# IO_and_Connectors.net
KiCad netlist of a schematic drawn in Altium Designer
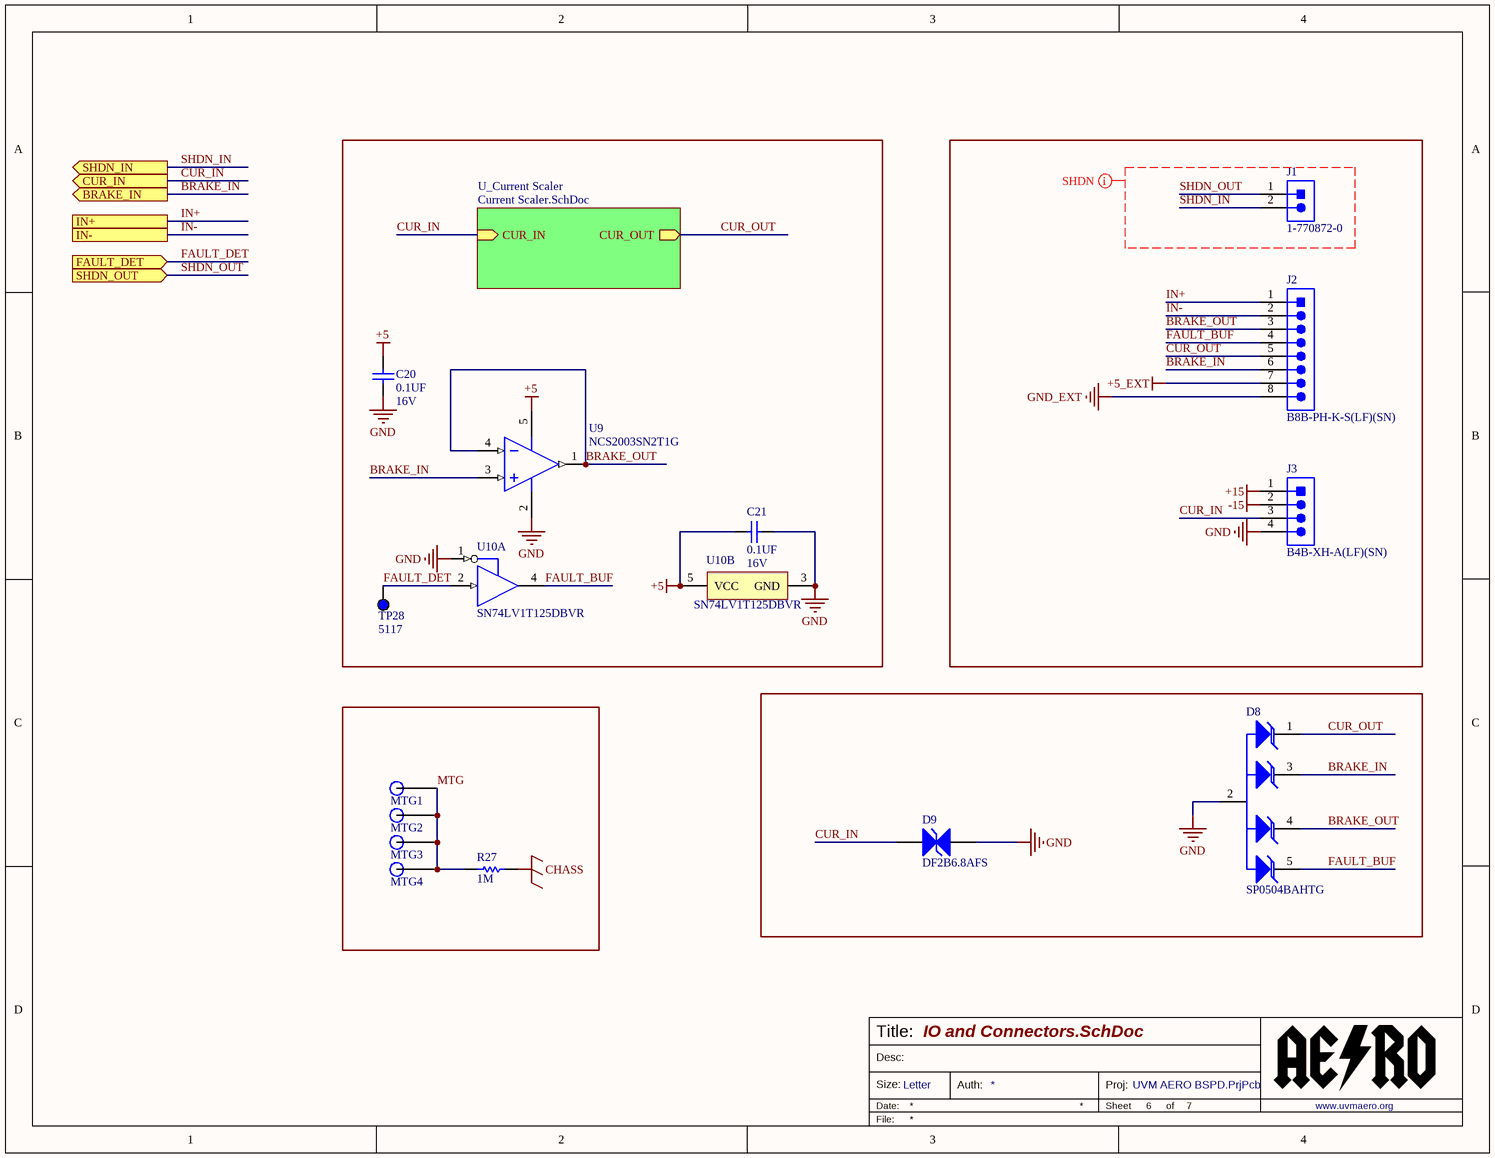
[diagram p0: IO and Connectors.SchDoc]

(export (version "E")
  (design (tool "Eeschema 10.0.6"))
  (components
    (comp (ref "C20")
      (value "CAP 0603 0.1UF 16V 10% X7R")
      (footprint "0603_CAP")
      (description "Capacitor Surface Mount 0603 Footprint 0.1UF 16V 10% Tolerance Ceramic X7R")
      (fields
        (field (name "VAL") "0.1UF")
        (field (name "VOL") "16V")
        (field (name "MANUFACTURER") "Various")
        (field (name "VOLTAGE") "16V")
      )
      (libsource (lib "Passive Components") (part "cap"))
    )
    (comp (ref "C21")
      (value "CAP 0603 0.1UF 16V 10% X7R")
      (footprint "0603_CAP")
      (description "Capacitor Surface Mount 0603 Footprint 0.1UF 16V 10% Tolerance Ceramic X7R")
      (fields
        (field (name "VAL") "0.1UF")
        (field (name "VOL") "16V")
        (field (name "MANUFACTURER") "Various")
        (field (name "VOLTAGE") "16V")
      )
      (libsource (lib "Passive Components") (part "cap"))
    )
    (comp (ref "D8")
      (value "SP0504BAHTG")
      (footprint "SOT23127P600-8N")
      (description "8.5V Clamp  Ipp Tvs Diode Surface Mount SOT-23-5 5.5V")
      (fields (field (name "MANUFACTURER") "Littelfuse"))
      (libsource (lib "bspd parts") (part "SP0504BAHTG"))
    )
    (comp (ref "D9")
      (value "DF2B6.8AFS")
      (footprint "SOD923")
      (description "7V (Typ) Clamp 1A (8/20µs) Ipp Tvs Diode Surface Mount fSC (SOD-923)")
      (libsource (lib "bspd parts") (part "DF2B6.8AFS"))
    )
    (comp (ref "J1")
      (value "1-770872-0")
      (footprint "CON2_1X2_P163_VM_ALT")
      (description "Connector Header Through Hole 2 position 0.163\" (4.14mm)")
      (fields (field (name "COPYRIGHT") "Copyright (C) 2018 Accelerated Designs. All rights reserved"))
      (libsource (lib "bspd parts") (part "1-770872-0"))
    )
    (comp (ref "J2")
      (value "B8B-PH-K-S(LF)(SN)")
      (footprint "B8B-PH-K")
      (description "Connector Header Through Hole 8 position 0.079\" (2.00mm)")
      (libsource (lib "bspd parts") (part "B8B-PH-K-S(LF)(SN)"))
    )
    (comp (ref "J3")
      (value "B4B-XH-A(LF)(SN)")
      (footprint "B4B-XH-A(LF)(SN)")
      (description "Connector Header Through Hole 4 position 0.098\" (2.50mm)")
      (fields (field (name "MANUFACTURER") "JST"))
      (libsource (lib "bspd parts") (part "B4B-XH-A(LF)(SN)"))
    )
    (comp (ref "MTG1")
      (value "PCB MTG M3")
      (footprint "MTG-M3")
      (description "PCB Mounting for M3 Screw")
      (libsource (lib "Hardware") (part "MTG"))
    )
    (comp (ref "MTG2")
      (value "PCB MTG M3")
      (footprint "MTG-M3")
      (description "PCB Mounting for M3 Screw")
      (libsource (lib "Hardware") (part "MTG"))
    )
    (comp (ref "MTG3")
      (value "PCB MTG M3")
      (footprint "MTG-M3")
      (description "PCB Mounting for M3 Screw")
      (libsource (lib "Hardware") (part "MTG"))
    )
    (comp (ref "MTG4")
      (value "PCB MTG M3")
      (footprint "MTG-M3")
      (description "PCB Mounting for M3 Screw")
      (libsource (lib "Hardware") (part "MTG"))
    )
    (comp (ref "R27")
      (value "1M")
      (footprint "RESC2013X60X35ML10T20")
      (fields (field (name "MANUFACTURER") "Yageo") (field (name "PART NUMBER") "RT0805BRE071ML"))
      (libsource (lib "Altium Content Vault") (part "RES"))
    )
    (comp (ref "TP28")
      (value "5117")
      (footprint "KSTN-5117")
      (description "Test Point, Blue, 1-Pin THD, RoHS, Bulk")
      (fields (field (name "MANUFACTURER") "KeystoneElectronics"))
      (libsource (lib "bspd parts") (part "5117"))
    )
    (comp (ref "U9")
      (value "NCS2003SN2T1G")
      (footprint "ONSC-TSOP-5-483-02_V")
      (fields (field (name "MANUFACTURER") "On Semiconductor"))
      (libsource (lib "Altium Content Vault") (part "ONSC-NCS2003-TSOP-5-483-02"))
    )
    (comp (ref "U10")
      (value "SN74LV1T125DBVR")
      (footprint "DBV0005A_M")
      (description "Single Power Supply, Single BUFFER GATE w/ 3-State Output (active low enable), DBV0005A, LARGE T&R")
      (fields
        (field (name "GENERIC PART NUMBER") "SN74LV1T125")
        (field (name "MANUFACTURER") "Texas Instruments")
      )
      (libsource (lib "Altium Content Vault") (part "TI-SN74AXXXX1X125-5"))
    )
  )
  (nets
    (net (code "1") (name "+5") (class "Default")
      (node (ref "C20") (pin "2") (pinfunction "2_2") (pintype "passive"))
      (node (ref "C21") (pin "2") (pinfunction "2_2") (pintype "passive"))
      (node (ref "U10") (pin "5") (pinfunction "VCC_5") (pintype "power_in"))
      (node (ref "U9") (pin "5") (pinfunction "VDD_5") (pintype "power_in"))
    )
    (net (code "2") (name "+5_EXT") (class "Default")
      (node (ref "J2") (pin "7") (pinfunction "7_7") (pintype "passive"))
    )
    (net (code "3") (name "+15") (class "Default")
      (node (ref "J3") (pin "1") (pinfunction "1_1") (pintype "passive"))
    )
    (net (code "4") (name "-15") (class "Default")
      (node (ref "J3") (pin "2") (pinfunction "2_2") (pintype "passive"))
    )
    (net (code "5") (name "/BRAKE_IN") (class "Default")
      (node (ref "D8") (pin "3") (pinfunction "3_3") (pintype "passive"))
      (node (ref "J2") (pin "6") (pinfunction "6_6") (pintype "passive"))
      (node (ref "U9") (pin "3") (pinfunction "IN+_3") (pintype "input"))
    )
    (net (code "6") (name "/BRAKE_OUT") (class "Default")
      (node (ref "D8") (pin "4") (pinfunction "4_4") (pintype "passive"))
      (node (ref "J2") (pin "3") (pinfunction "3_3") (pintype "passive"))
      (node (ref "U9") (pin "1") (pinfunction "VOUT_1") (pintype "output"))
      (node (ref "U9") (pin "4") (pinfunction "IN-_4") (pintype "input"))
    )
    (net (code "7") (name "/CUR_IN") (class "Default")
      (node (ref "D9") (pin "1") (pinfunction "A1_1") (pintype "passive"))
      (node (ref "J3") (pin "3") (pinfunction "3_3") (pintype "passive"))
    )
    (net (code "8") (name "/CUR_OUT") (class "Default")
      (node (ref "D8") (pin "1") (pinfunction "1_1") (pintype "passive"))
      (node (ref "J2") (pin "5") (pinfunction "5_5") (pintype "passive"))
    )
    (net (code "9") (name "/FAULT_BUF") (class "Default")
      (node (ref "D8") (pin "5") (pinfunction "5_5") (pintype "passive"))
      (node (ref "J2") (pin "4") (pinfunction "4_4") (pintype "passive"))
      (node (ref "U10") (pin "4") (pinfunction "Y_4") (pintype "tri_state"))
    )
    (net (code "10") (name "/FAULT_DET") (class "Default")
      (node (ref "TP28") (pin "1") (pintype "passive"))
      (node (ref "U10") (pin "2") (pinfunction "A_2") (pintype "input"))
    )
    (net (code "11") (name "/IN+") (class "Default")
      (node (ref "J2") (pin "1") (pinfunction "1_1") (pintype "passive"))
    )
    (net (code "12") (name "/IN-") (class "Default")
      (node (ref "J2") (pin "2") (pinfunction "2_2") (pintype "passive"))
    )
    (net (code "13") (name "/MTG") (class "Default")
      (node (ref "MTG1") (pin "1") (pinfunction "1_1") (pintype "passive"))
      (node (ref "MTG2") (pin "1") (pinfunction "1_1") (pintype "passive"))
      (node (ref "MTG3") (pin "1") (pinfunction "1_1") (pintype "passive"))
      (node (ref "MTG4") (pin "1") (pinfunction "1_1") (pintype "passive"))
      (node (ref "R27") (pin "2") (pinfunction "2_2") (pintype "passive"))
    )
    (net (code "14") (name "/SHDN_IN") (class "Default")
      (node (ref "J1") (pin "2") (pinfunction "2_2") (pintype "passive"))
    )
    (net (code "15") (name "/SHDN_OUT") (class "Default")
      (node (ref "J1") (pin "1") (pinfunction "1_1") (pintype "passive"))
    )
    (net (code "16") (name "CHASS") (class "Default")
      (node (ref "R27") (pin "1") (pinfunction "1_1") (pintype "passive"))
    )
    (net (code "17") (name "GND") (class "Default")
      (node (ref "C20") (pin "1") (pinfunction "1_1") (pintype "passive"))
      (node (ref "C21") (pin "1") (pinfunction "1_1") (pintype "passive"))
      (node (ref "D8") (pin "2") (pinfunction "2_2") (pintype "passive"))
      (node (ref "D9") (pin "2") (pinfunction "A2_2") (pintype "passive"))
      (node (ref "J3") (pin "4") (pinfunction "4_4") (pintype "passive"))
      (node (ref "U10") (pin "1") (pinfunction "~{OE}_1") (pintype "input"))
      (node (ref "U10") (pin "3") (pinfunction "GND_3") (pintype "power_in"))
      (node (ref "U9") (pin "2") (pinfunction "VSS_2") (pintype "power_in"))
    )
    (net (code "18") (name "GND_EXT") (class "Default")
      (node (ref "J2") (pin "8") (pinfunction "8_8") (pintype "passive"))
    )
  )
)
